# base.net
KiCad netlist of a schematic drawn in Altium Designer
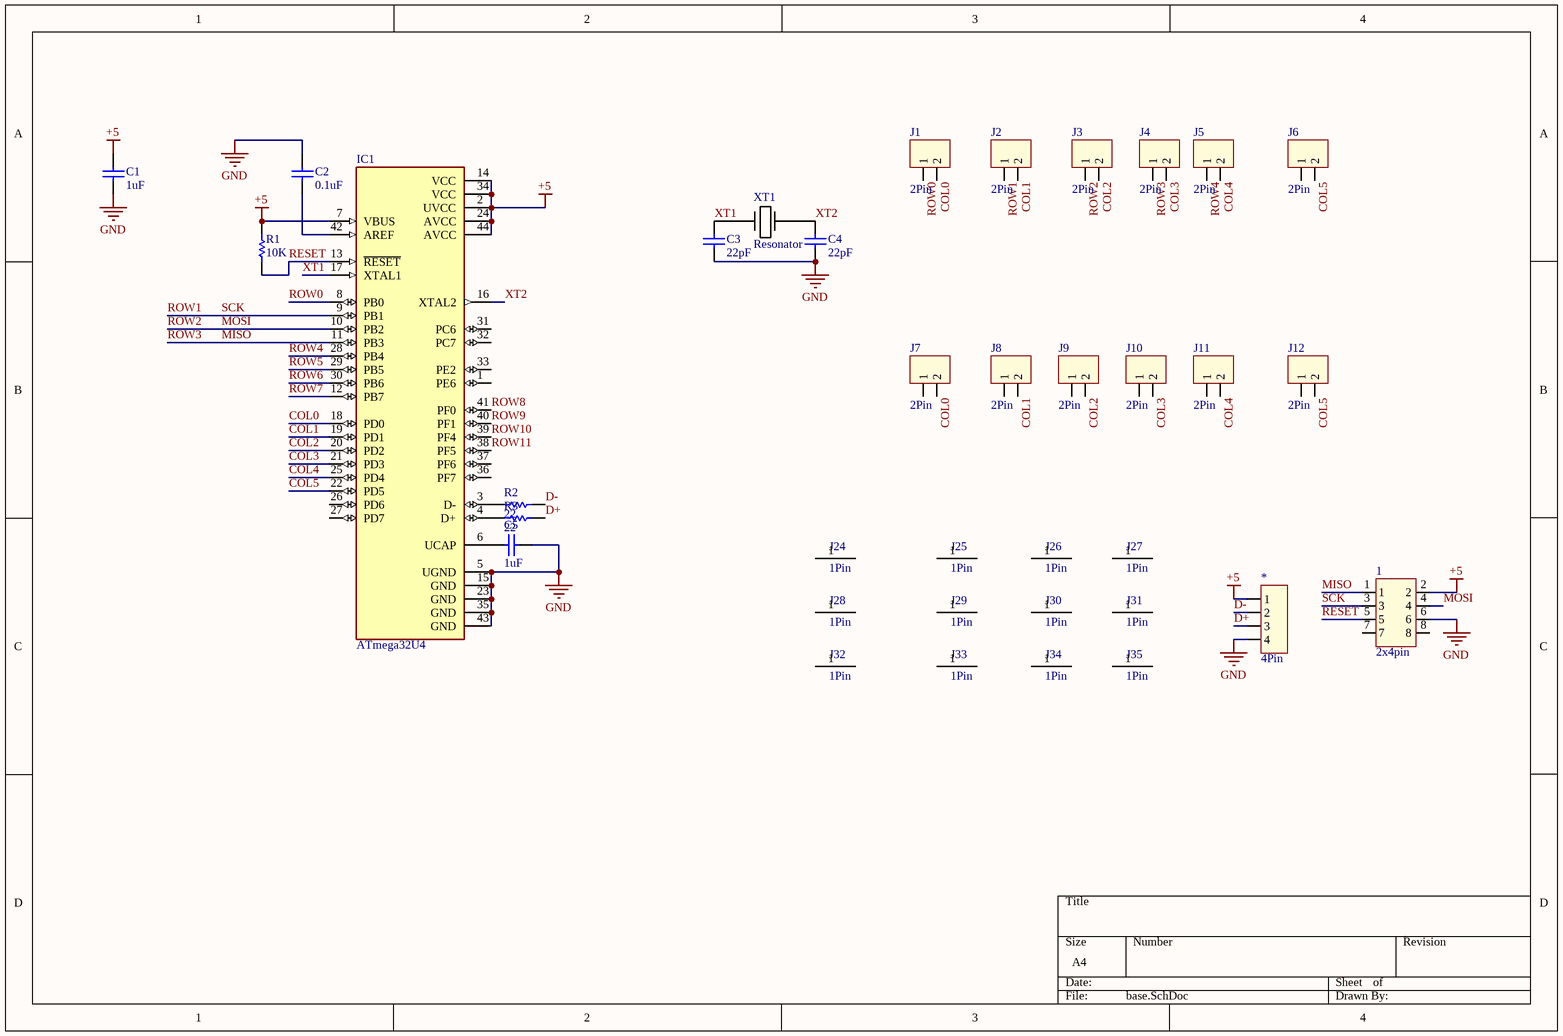
[diagram p0: base.SchDoc]

(export (version "E")
  (design (tool "Eeschema 10.0.6"))
  (components
    (comp (ref "*")
      (value "4Pin")
      (footprint "XH2.54-4pin")
      (libsource (lib "MyOwnSchlib_ver1.2") (part "4Pin"))
    )
    (comp (ref "1")
      (value "2x4pin")
      (footprint "4pin_slot")
      (libsource (lib "MyOwnSchlib_ver1.2") (part "2x4pin"))
    )
    (comp (ref "C1") (value "1uF") (footprint "C0805") (libsource (lib "MyOwnSchlib_ver1.2") (part "Cap")))
    (comp (ref "C2") (value "0.1uF") (footprint "C0805") (libsource (lib "MyOwnSchlib_ver1.2") (part "Cap")))
    (comp (ref "C3") (value "22pF") (footprint "C0805") (libsource (lib "MyOwnSchlib_ver1.2") (part "Cap")))
    (comp (ref "C4") (value "22pF") (footprint "C0805") (libsource (lib "MyOwnSchlib_ver1.2") (part "Cap")))
    (comp (ref "C5") (value "1uF") (footprint "C0805") (libsource (lib "MyOwnSchlib_ver1.2") (part "Cap")))
    (comp (ref "IC1")
      (value "ATmega32U4")
      (footprint "TQFP-44")
      (libsource (lib "MyOwnSchlib_ver1.2") (part "ATmega32U4"))
    )
    (comp (ref "J1")
      (value "2Pin")
      (footprint "TH2.54-2pin")
      (libsource (lib "MyOwnSchlib_ver1.2") (part "2Pin"))
    )
    (comp (ref "J2")
      (value "2Pin")
      (footprint "TH2.54-2pin")
      (libsource (lib "MyOwnSchlib_ver1.2") (part "2Pin"))
    )
    (comp (ref "J3")
      (value "2Pin")
      (footprint "TH2.54-2pin")
      (libsource (lib "MyOwnSchlib_ver1.2") (part "2Pin"))
    )
    (comp (ref "J4")
      (value "2Pin")
      (footprint "TH2.54-2pin")
      (libsource (lib "MyOwnSchlib_ver1.2") (part "2Pin"))
    )
    (comp (ref "J5")
      (value "2Pin")
      (footprint "TH2.54-2pin")
      (libsource (lib "MyOwnSchlib_ver1.2") (part "2Pin"))
    )
    (comp (ref "J6")
      (value "2Pin")
      (footprint "TH2.54-2pin")
      (libsource (lib "MyOwnSchlib_ver1.2") (part "2Pin"))
    )
    (comp (ref "J7")
      (value "2Pin")
      (footprint "TH2.54-2pin")
      (libsource (lib "MyOwnSchlib_ver1.2") (part "2Pin"))
    )
    (comp (ref "J8")
      (value "2Pin")
      (footprint "TH2.54-2pin")
      (libsource (lib "MyOwnSchlib_ver1.2") (part "2Pin"))
    )
    (comp (ref "J9")
      (value "2Pin")
      (footprint "TH2.54-2pin")
      (libsource (lib "MyOwnSchlib_ver1.2") (part "2Pin"))
    )
    (comp (ref "J10")
      (value "2Pin")
      (footprint "TH2.54-2pin")
      (libsource (lib "MyOwnSchlib_ver1.2") (part "2Pin"))
    )
    (comp (ref "J11")
      (value "2Pin")
      (footprint "TH2.54-2pin")
      (libsource (lib "MyOwnSchlib_ver1.2") (part "2Pin"))
    )
    (comp (ref "J12")
      (value "2Pin")
      (footprint "TH2.54-2pin")
      (libsource (lib "MyOwnSchlib_ver1.2") (part "2Pin"))
    )
    (comp (ref "J24") (value "1Pin") (footprint "1Pin") (libsource (lib "MyOwnSchlib_ver1.2") (part "1Pin")))
    (comp (ref "J25") (value "1Pin") (footprint "1Pin") (libsource (lib "MyOwnSchlib_ver1.2") (part "1Pin")))
    (comp (ref "J26") (value "1Pin") (footprint "1Pin") (libsource (lib "MyOwnSchlib_ver1.2") (part "1Pin")))
    (comp (ref "J27") (value "1Pin") (footprint "1Pin") (libsource (lib "MyOwnSchlib_ver1.2") (part "1Pin")))
    (comp (ref "J28") (value "1Pin") (footprint "1Pin") (libsource (lib "MyOwnSchlib_ver1.2") (part "1Pin")))
    (comp (ref "J29") (value "1Pin") (footprint "1Pin") (libsource (lib "MyOwnSchlib_ver1.2") (part "1Pin")))
    (comp (ref "J30") (value "1Pin") (footprint "1Pin") (libsource (lib "MyOwnSchlib_ver1.2") (part "1Pin")))
    (comp (ref "J31") (value "1Pin") (footprint "1Pin") (libsource (lib "MyOwnSchlib_ver1.2") (part "1Pin")))
    (comp (ref "J32") (value "1Pin") (footprint "1Pin") (libsource (lib "MyOwnSchlib_ver1.2") (part "1Pin")))
    (comp (ref "J33") (value "1Pin") (footprint "1Pin") (libsource (lib "MyOwnSchlib_ver1.2") (part "1Pin")))
    (comp (ref "J34") (value "1Pin") (footprint "1Pin") (libsource (lib "MyOwnSchlib_ver1.2") (part "1Pin")))
    (comp (ref "J35") (value "1Pin") (footprint "1Pin") (libsource (lib "MyOwnSchlib_ver1.2") (part "1Pin")))
    (comp (ref "R1")
      (value "10K")
      (footprint "R0805")
      (libsource (lib "MyOwnSchlib_ver1.2") (part "Resistor"))
    )
    (comp (ref "R2")
      (value "22")
      (footprint "R0805")
      (libsource (lib "MyOwnSchlib_ver1.2") (part "Resistor"))
    )
    (comp (ref "R3")
      (value "22")
      (footprint "R0805")
      (libsource (lib "MyOwnSchlib_ver1.2") (part "Resistor"))
    )
    (comp (ref "XT1")
      (value "Resonator")
      (footprint "Resonator")
      (libsource (lib "MyOwnSchlib_ver1.2") (part "Resonator"))
    )
  )
  (nets
    (net (code "1") (name "+5") (class "Default")
      (node (ref "*") (pin "1") (pinfunction "1_1") (pintype "passive"))
      (node (ref "1") (pin "2") (pinfunction "2_2") (pintype "passive"))
      (node (ref "C1") (pin "2") (pinfunction "2_2") (pintype "passive"))
      (node (ref "IC1") (pin "14") (pinfunction "VCC_14") (pintype "power_in"))
      (node (ref "IC1") (pin "2") (pinfunction "UVCC_2") (pintype "power_in"))
      (node (ref "IC1") (pin "24") (pinfunction "AVCC_24") (pintype "power_in"))
      (node (ref "IC1") (pin "34") (pinfunction "VCC_34") (pintype "power_in"))
      (node (ref "IC1") (pin "44") (pinfunction "AVCC_44") (pintype "power_in"))
      (node (ref "IC1") (pin "7") (pinfunction "VBUS_7") (pintype "input"))
      (node (ref "R1") (pin "2") (pinfunction "2_2") (pintype "passive"))
    )
    (net (code "2") (name "/COL0") (class "Default")
      (node (ref "IC1") (pin "18") (pinfunction "PD0_18") (pintype "bidirectional"))
      (node (ref "J1") (pin "2") (pinfunction "2_2") (pintype "passive"))
      (node (ref "J7") (pin "2") (pinfunction "2_2") (pintype "passive"))
    )
    (net (code "3") (name "/COL1") (class "Default")
      (node (ref "IC1") (pin "19") (pinfunction "PD1_19") (pintype "bidirectional"))
      (node (ref "J2") (pin "2") (pinfunction "2_2") (pintype "passive"))
      (node (ref "J8") (pin "2") (pinfunction "2_2") (pintype "passive"))
    )
    (net (code "4") (name "/COL2") (class "Default")
      (node (ref "IC1") (pin "20") (pinfunction "PD2_20") (pintype "bidirectional"))
      (node (ref "J3") (pin "2") (pinfunction "2_2") (pintype "passive"))
      (node (ref "J9") (pin "2") (pinfunction "2_2") (pintype "passive"))
    )
    (net (code "5") (name "/COL3") (class "Default")
      (node (ref "IC1") (pin "21") (pinfunction "PD3_21") (pintype "bidirectional"))
      (node (ref "J10") (pin "2") (pinfunction "2_2") (pintype "passive"))
      (node (ref "J4") (pin "2") (pinfunction "2_2") (pintype "passive"))
    )
    (net (code "6") (name "/COL4") (class "Default")
      (node (ref "IC1") (pin "25") (pinfunction "PD4_25") (pintype "bidirectional"))
      (node (ref "J11") (pin "2") (pinfunction "2_2") (pintype "passive"))
      (node (ref "J5") (pin "2") (pinfunction "2_2") (pintype "passive"))
    )
    (net (code "7") (name "/COL5") (class "Default")
      (node (ref "IC1") (pin "22") (pinfunction "PD5_22") (pintype "bidirectional"))
      (node (ref "J12") (pin "2") (pinfunction "2_2") (pintype "passive"))
      (node (ref "J6") (pin "2") (pinfunction "2_2") (pintype "passive"))
    )
    (net (code "8") (name "/D+") (class "Default")
      (node (ref "*") (pin "3") (pinfunction "3_3") (pintype "passive"))
      (node (ref "R3") (pin "2") (pinfunction "2_2") (pintype "passive"))
    )
    (net (code "9") (name "/D-") (class "Default")
      (node (ref "*") (pin "2") (pinfunction "2_2") (pintype "passive"))
      (node (ref "R2") (pin "2") (pinfunction "2_2") (pintype "passive"))
    )
    (net (code "10") (name "/MISO") (class "Default")
      (node (ref "1") (pin "1") (pinfunction "1_1") (pintype "passive"))
      (node (ref "IC1") (pin "11") (pinfunction "PB3_11") (pintype "bidirectional"))
      (node (ref "J4") (pin "1") (pinfunction "1_1") (pintype "passive"))
    )
    (net (code "11") (name "/MOSI") (class "Default")
      (node (ref "1") (pin "4") (pinfunction "4_4") (pintype "passive"))
      (node (ref "IC1") (pin "10") (pinfunction "PB2_10") (pintype "bidirectional"))
      (node (ref "J3") (pin "1") (pinfunction "1_1") (pintype "passive"))
    )
    (net (code "12") (name "/RESET") (class "Default")
      (node (ref "1") (pin "5") (pinfunction "5_5") (pintype "passive"))
      (node (ref "IC1") (pin "13") (pinfunction "~{RESET}_13") (pintype "input"))
      (node (ref "R1") (pin "1") (pinfunction "1_1") (pintype "passive"))
    )
    (net (code "13") (name "/ROW0") (class "Default")
      (node (ref "IC1") (pin "8") (pinfunction "PB0_8") (pintype "bidirectional"))
      (node (ref "J1") (pin "1") (pinfunction "1_1") (pintype "passive"))
    )
    (net (code "14") (name "/ROW1") (class "Default")
      (node (ref "1") (pin "3") (pinfunction "3_3") (pintype "passive"))
      (node (ref "IC1") (pin "9") (pinfunction "PB1_9") (pintype "bidirectional"))
      (node (ref "J2") (pin "1") (pinfunction "1_1") (pintype "passive"))
    )
    (net (code "15") (name "/ROW4") (class "Default")
      (node (ref "IC1") (pin "28") (pinfunction "PB4_28") (pintype "bidirectional"))
      (node (ref "J5") (pin "1") (pinfunction "1_1") (pintype "passive"))
    )
    (net (code "16") (name "/ROW5") (class "Default")
      (node (ref "IC1") (pin "29") (pinfunction "PB5_29") (pintype "bidirectional"))
    )
    (net (code "17") (name "/ROW6") (class "Default")
      (node (ref "IC1") (pin "30") (pinfunction "PB6_30") (pintype "bidirectional"))
    )
    (net (code "18") (name "/ROW7") (class "Default")
      (node (ref "IC1") (pin "12") (pinfunction "PB7_12") (pintype "bidirectional"))
    )
    (net (code "19") (name "/ROW8") (class "Default")
      (node (ref "IC1") (pin "41") (pinfunction "PF0_41") (pintype "bidirectional"))
    )
    (net (code "20") (name "/ROW9") (class "Default")
      (node (ref "IC1") (pin "40") (pinfunction "PF1_40") (pintype "bidirectional"))
    )
    (net (code "21") (name "/ROW10") (class "Default")
      (node (ref "IC1") (pin "39") (pinfunction "PF4_39") (pintype "bidirectional"))
    )
    (net (code "22") (name "/ROW11") (class "Default")
      (node (ref "IC1") (pin "38") (pinfunction "PF5_38") (pintype "bidirectional"))
    )
    (net (code "23") (name "/XT1") (class "Default")
      (node (ref "C3") (pin "2") (pinfunction "2_2") (pintype "passive"))
      (node (ref "IC1") (pin "17") (pinfunction "XTAL1_17") (pintype "input"))
      (node (ref "XT1") (pin "1") (pinfunction "1_1") (pintype "passive"))
    )
    (net (code "24") (name "/XT2") (class "Default")
      (node (ref "C4") (pin "2") (pinfunction "2_2") (pintype "passive"))
      (node (ref "IC1") (pin "16") (pinfunction "XTAL2_16") (pintype "output"))
      (node (ref "XT1") (pin "2") (pinfunction "2_2") (pintype "passive"))
    )
    (net (code "25") (name "GND") (class "Default")
      (node (ref "*") (pin "4") (pinfunction "4_4") (pintype "passive"))
      (node (ref "1") (pin "6") (pinfunction "6_6") (pintype "passive"))
      (node (ref "C1") (pin "1") (pinfunction "1_1") (pintype "passive"))
      (node (ref "C2") (pin "2") (pinfunction "2_2") (pintype "passive"))
      (node (ref "C3") (pin "1") (pinfunction "1_1") (pintype "passive"))
      (node (ref "C4") (pin "1") (pinfunction "1_1") (pintype "passive"))
      (node (ref "C5") (pin "2") (pinfunction "2_2") (pintype "passive"))
      (node (ref "IC1") (pin "15") (pinfunction "GND_15") (pintype "power_in"))
      (node (ref "IC1") (pin "23") (pinfunction "GND_23") (pintype "power_in"))
      (node (ref "IC1") (pin "35") (pinfunction "GND_35") (pintype "power_in"))
      (node (ref "IC1") (pin "43") (pinfunction "GND_43") (pintype "power_in"))
      (node (ref "IC1") (pin "5") (pinfunction "UGND_5") (pintype "power_in"))
    )
    (net (code "26") (name "Net-(IC1-AREF)") (class "Default")
      (node (ref "C2") (pin "1") (pinfunction "1_1") (pintype "passive"))
      (node (ref "IC1") (pin "42") (pinfunction "AREF_42") (pintype "input"))
    )
    (net (code "27") (name "Net-(IC1-D+)") (class "Default")
      (node (ref "IC1") (pin "4") (pinfunction "D+_4") (pintype "bidirectional"))
      (node (ref "R3") (pin "1") (pinfunction "1_1") (pintype "passive"))
    )
    (net (code "28") (name "Net-(IC1-D-)") (class "Default")
      (node (ref "IC1") (pin "3") (pinfunction "D-_3") (pintype "bidirectional"))
      (node (ref "R2") (pin "1") (pinfunction "1_1") (pintype "passive"))
    )
    (net (code "29") (name "Net-(IC1-UCAP)") (class "Default")
      (node (ref "C5") (pin "1") (pinfunction "1_1") (pintype "passive"))
      (node (ref "IC1") (pin "6") (pinfunction "UCAP_6") (pintype "passive"))
    )
    (net (code "30") (name "unconnected-(1-Pad7)") (class "Default")
      (node (ref "1") (pin "7") (pinfunction "7_7") (pintype "passive"))
    )
    (net (code "31") (name "unconnected-(1-Pad8)") (class "Default")
      (node (ref "1") (pin "8") (pinfunction "8_8") (pintype "passive"))
    )
    (net (code "32") (name "unconnected-(IC1-PC6-Pad31)") (class "Default")
      (node (ref "IC1") (pin "31") (pinfunction "PC6_31") (pintype "bidirectional"))
    )
    (net (code "33") (name "unconnected-(IC1-PC7-Pad32)") (class "Default")
      (node (ref "IC1") (pin "32") (pinfunction "PC7_32") (pintype "bidirectional"))
    )
    (net (code "34") (name "unconnected-(IC1-PD6-Pad26)") (class "Default")
      (node (ref "IC1") (pin "26") (pinfunction "PD6_26") (pintype "bidirectional"))
    )
    (net (code "35") (name "unconnected-(IC1-PD7-Pad27)") (class "Default")
      (node (ref "IC1") (pin "27") (pinfunction "PD7_27") (pintype "bidirectional"))
    )
    (net (code "36") (name "unconnected-(IC1-PE2-Pad33)") (class "Default")
      (node (ref "IC1") (pin "33") (pinfunction "PE2_33") (pintype "bidirectional"))
    )
    (net (code "37") (name "unconnected-(IC1-PE6-Pad1)") (class "Default")
      (node (ref "IC1") (pin "1") (pinfunction "PE6_1") (pintype "bidirectional"))
    )
    (net (code "38") (name "unconnected-(IC1-PF6-Pad37)") (class "Default")
      (node (ref "IC1") (pin "37") (pinfunction "PF6_37") (pintype "bidirectional"))
    )
    (net (code "39") (name "unconnected-(IC1-PF7-Pad36)") (class "Default")
      (node (ref "IC1") (pin "36") (pinfunction "PF7_36") (pintype "bidirectional"))
    )
    (net (code "40") (name "unconnected-(J6-Pad1)") (class "Default")
      (node (ref "J6") (pin "1") (pinfunction "1_1") (pintype "passive"))
    )
    (net (code "41") (name "unconnected-(J7-Pad1)") (class "Default")
      (node (ref "J7") (pin "1") (pinfunction "1_1") (pintype "passive"))
    )
    (net (code "42") (name "unconnected-(J8-Pad1)") (class "Default")
      (node (ref "J8") (pin "1") (pinfunction "1_1") (pintype "passive"))
    )
    (net (code "43") (name "unconnected-(J9-Pad1)") (class "Default")
      (node (ref "J9") (pin "1") (pinfunction "1_1") (pintype "passive"))
    )
    (net (code "44") (name "unconnected-(J10-Pad1)") (class "Default")
      (node (ref "J10") (pin "1") (pinfunction "1_1") (pintype "passive"))
    )
    (net (code "45") (name "unconnected-(J11-Pad1)") (class "Default")
      (node (ref "J11") (pin "1") (pinfunction "1_1") (pintype "passive"))
    )
    (net (code "46") (name "unconnected-(J12-Pad1)") (class "Default")
      (node (ref "J12") (pin "1") (pinfunction "1_1") (pintype "passive"))
    )
    (net (code "47") (name "unconnected-(J24-0-Pad1)") (class "Default")
      (node (ref "J24") (pin "1") (pinfunction "0_1") (pintype "passive"))
    )
    (net (code "48") (name "unconnected-(J25-0-Pad1)") (class "Default")
      (node (ref "J25") (pin "1") (pinfunction "0_1") (pintype "passive"))
    )
    (net (code "49") (name "unconnected-(J26-0-Pad1)") (class "Default")
      (node (ref "J26") (pin "1") (pinfunction "0_1") (pintype "passive"))
    )
    (net (code "50") (name "unconnected-(J27-0-Pad1)") (class "Default")
      (node (ref "J27") (pin "1") (pinfunction "0_1") (pintype "passive"))
    )
    (net (code "51") (name "unconnected-(J28-0-Pad1)") (class "Default")
      (node (ref "J28") (pin "1") (pinfunction "0_1") (pintype "passive"))
    )
    (net (code "52") (name "unconnected-(J29-0-Pad1)") (class "Default")
      (node (ref "J29") (pin "1") (pinfunction "0_1") (pintype "passive"))
    )
    (net (code "53") (name "unconnected-(J30-0-Pad1)") (class "Default")
      (node (ref "J30") (pin "1") (pinfunction "0_1") (pintype "passive"))
    )
    (net (code "54") (name "unconnected-(J31-0-Pad1)") (class "Default")
      (node (ref "J31") (pin "1") (pinfunction "0_1") (pintype "passive"))
    )
    (net (code "55") (name "unconnected-(J32-0-Pad1)") (class "Default")
      (node (ref "J32") (pin "1") (pinfunction "0_1") (pintype "passive"))
    )
    (net (code "56") (name "unconnected-(J33-0-Pad1)") (class "Default")
      (node (ref "J33") (pin "1") (pinfunction "0_1") (pintype "passive"))
    )
    (net (code "57") (name "unconnected-(J34-0-Pad1)") (class "Default")
      (node (ref "J34") (pin "1") (pinfunction "0_1") (pintype "passive"))
    )
    (net (code "58") (name "unconnected-(J35-0-Pad1)") (class "Default")
      (node (ref "J35") (pin "1") (pinfunction "0_1") (pintype "passive"))
    )
  )
)
